# for_description.net
KiCad netlist of a schematic drawn in Altium Designer
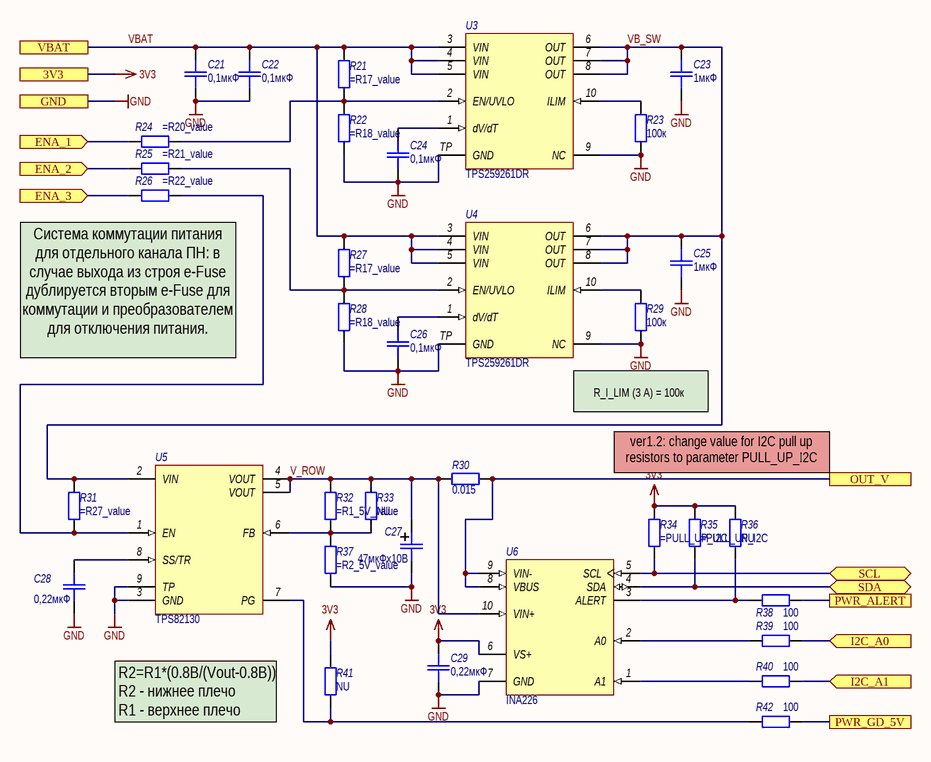
[diagram p0: for description.SchDoc]

(export (version "E")
  (design (tool "Eeschema 10.0.6"))
  (components
    (comp (ref "C21")
      (value "0,1мкФ")
      (footprint "CR-0603")
      (description "Конденсатор для поверхностного монтажа")
      (libsource (lib "my_passive") (part "C_smd"))
    )
    (comp (ref "C22")
      (value "0,1мкФ")
      (footprint "CR-0603")
      (description "Конденсатор для поверхностного монтажа")
      (libsource (lib "my_passive") (part "C_smd"))
    )
    (comp (ref "C23")
      (value "1мкФ")
      (footprint "CR-0603")
      (description "Конденсатор для поверхностного монтажа")
      (libsource (lib "my_passive") (part "C_smd"))
    )
    (comp (ref "C24")
      (value "0,1мкФ")
      (footprint "CR-0603")
      (description "Конденсатор для поверхностного монтажа")
      (libsource (lib "my_passive") (part "C_smd"))
    )
    (comp (ref "C25")
      (value "1мкФ")
      (footprint "CR-0603")
      (description "Конденсатор для поверхностного монтажа")
      (libsource (lib "my_passive") (part "C_smd"))
    )
    (comp (ref "C26")
      (value "0,1мкФ")
      (footprint "CR-0603")
      (description "Конденсатор для поверхностного монтажа")
      (libsource (lib "my_passive") (part "C_smd"))
    )
    (comp (ref "C27")
      (value "47мкФх10В")
      (footprint "C_SMD_SIZE_B")
      (description "Поляризованный конеднсатор для поверхностного монтажа")
      (libsource (lib "my_passive") (part "C_pol_smd"))
    )
    (comp (ref "C28")
      (value "0,22мкФ")
      (footprint "CR-0603")
      (description "Конденсатор для поверхностного монтажа")
      (libsource (lib "my_passive") (part "C_smd"))
    )
    (comp (ref "C29")
      (value "0,22мкФ")
      (footprint "CR-0603")
      (description "Конденсатор для поверхностного монтажа")
      (libsource (lib "my_passive") (part "C_smd"))
    )
    (comp (ref "R21")
      (value "R17_value")
      (footprint "CR-0603")
      (description "Резистор для поверхностного монтажа")
      (libsource (lib "my_passive") (part "R_smd"))
    )
    (comp (ref "R22")
      (value "R18_value")
      (footprint "CR-0603")
      (description "Резистор для поверхностного монтажа")
      (libsource (lib "my_passive") (part "R_smd"))
    )
    (comp (ref "R23")
      (value "100к")
      (footprint "CR-0603")
      (description "Резистор для поверхностного монтажа")
      (libsource (lib "") (part "R_smd_2"))
    )
    (comp (ref "R24")
      (value "~")
      (footprint "CR-0603")
      (description "Резистор для поверхностного монтажа")
      (libsource (lib "") (part "R_smd_1"))
    )
    (comp (ref "R25")
      (value "~")
      (footprint "CR-0603")
      (description "Резистор для поверхностного монтажа")
      (libsource (lib "") (part "R_smd_1"))
    )
    (comp (ref "R26")
      (value "~")
      (footprint "CR-0603")
      (description "Резистор для поверхностного монтажа")
      (libsource (lib "") (part "R_smd_1"))
    )
    (comp (ref "R27")
      (value "R17_value")
      (footprint "CR-0603")
      (description "Резистор для поверхностного монтажа")
      (libsource (lib "my_passive") (part "R_smd"))
    )
    (comp (ref "R28")
      (value "R18_value")
      (footprint "CR-0603")
      (description "Резистор для поверхностного монтажа")
      (libsource (lib "my_passive") (part "R_smd"))
    )
    (comp (ref "R29")
      (value "100к")
      (footprint "CR-0603")
      (description "Резистор для поверхностного монтажа")
      (libsource (lib "") (part "R_smd_2"))
    )
    (comp (ref "R30")
      (value "0.015")
      (footprint "CR-1206")
      (description "Резистор для поверхностного монтажа")
      (fields (field (name "Comment") "0,01"))
      (libsource (lib "") (part "R_smd_1"))
    )
    (comp (ref "R31")
      (value "~")
      (footprint "CR-0603")
      (description "Резистор для поверхностного монтажа")
      (libsource (lib "") (part "R_smd_2"))
    )
    (comp (ref "R32")
      (value "~")
      (footprint "CR-0603")
      (description "Резистор для поверхностного монтажа")
      (libsource (lib "") (part "R_smd_2"))
    )
    (comp (ref "R33")
      (value "NU")
      (footprint "CR-0603")
      (description "Резистор для поверхностного монтажа")
      (libsource (lib "") (part "R_smd_2"))
    )
    (comp (ref "R34")
      (value "~")
      (footprint "CR-0603")
      (description "Резистор для поверхностного монтажа")
      (libsource (lib "") (part "R_smd_2"))
    )
    (comp (ref "R35")
      (value "~")
      (footprint "CR-0603")
      (description "Резистор для поверхностного монтажа")
      (libsource (lib "") (part "R_smd_2"))
    )
    (comp (ref "R36")
      (value "NU")
      (footprint "CR-0603")
      (description "Резистор для поверхностного монтажа")
      (libsource (lib "") (part "R_smd_2"))
    )
    (comp (ref "R37")
      (value "~")
      (footprint "CR-0603")
      (description "Резистор для поверхностного монтажа")
      (libsource (lib "") (part "R_smd_2"))
    )
    (comp (ref "R38")
      (value "100")
      (footprint "CR-0603")
      (description "Резистор для поверхностного монтажа")
      (libsource (lib "") (part "R_smd_1"))
    )
    (comp (ref "R39")
      (value "100")
      (footprint "CR-0603")
      (description "Резистор для поверхностного монтажа")
      (libsource (lib "") (part "R_smd_1"))
    )
    (comp (ref "R40")
      (value "100")
      (footprint "CR-0603")
      (description "Резистор для поверхностного монтажа")
      (libsource (lib "") (part "R_smd_1"))
    )
    (comp (ref "R41")
      (value "NU")
      (footprint "CR-0603")
      (description "Резистор для поверхностного монтажа")
      (libsource (lib "") (part "R_smd_2"))
    )
    (comp (ref "R42")
      (value "100")
      (footprint "CR-0603")
      (description "Резистор для поверхностного монтажа")
      (libsource (lib "") (part "R_smd_1"))
    )
    (comp (ref "U3")
      (value "TPS259261ВК")
      (footprint "VSON-10")
      (description "Simple 5-V/12-V eFuse Protection Switches")
      (fields (field (name "НАИМЕНОВАНИЕ") "TPS259261DR"))
      (libsource (lib "my_power") (part "TPS259261"))
    )
    (comp (ref "U4")
      (value "TPS259261ВК")
      (footprint "VSON-10")
      (description "Simple 5-V/12-V eFuse Protection Switches")
      (fields (field (name "НАИМЕНОВАНИЕ") "TPS259261DR"))
      (libsource (lib "my_power") (part "TPS259261"))
    )
    (comp (ref "U5")
      (value "TPS82130")
      (footprint "uSiL-8")
      (description "17-V Input 3-A Step-Down Converter MicroSiP™ Module with Integrated Inductor")
      (fields (field (name "НАИМЕНОВАНИЕ") "TPS82130"))
      (libsource (lib "my_power") (part "TPS82130"))
    )
    (comp (ref "U6")
      (value "INA226")
      (footprint "VSSOP-8")
      (description "High- or Low-Side Measurement, Bidirectional Current and Power Monitor With I2C Interface")
      (fields (field (name "НАИМЕНОВАНИЕ") "INA226"))
      (libsource (lib "my_power") (part "INA226"))
    )
  )
  (nets
    (net (code "1") (name "/ENA_1") (class "Default")
      (node (ref "R24") (pin "2") (pinfunction "2_2") (pintype "passive"))
    )
    (net (code "2") (name "/ENA_2") (class "Default")
      (node (ref "R25") (pin "2") (pinfunction "2_2") (pintype "passive"))
    )
    (net (code "3") (name "/ENA_3") (class "Default")
      (node (ref "R26") (pin "2") (pinfunction "2_2") (pintype "passive"))
    )
    (net (code "4") (name "/I2C_A0") (class "Default")
      (node (ref "R39") (pin "1") (pinfunction "1_1") (pintype "passive"))
    )
    (net (code "5") (name "/I2C_A1") (class "Default")
      (node (ref "R40") (pin "1") (pinfunction "1_1") (pintype "passive"))
    )
    (net (code "6") (name "/OUT_V") (class "Default")
      (node (ref "R30") (pin "1") (pinfunction "1_1") (pintype "passive"))
      (node (ref "U6") (pin "8") (pinfunction "VBUS_8") (pintype "input"))
      (node (ref "U6") (pin "9") (pinfunction "VIN-_9") (pintype "input"))
    )
    (net (code "7") (name "/PWR_ALERT") (class "Default")
      (node (ref "R38") (pin "1") (pinfunction "1_1") (pintype "passive"))
    )
    (net (code "8") (name "/PWR_GD_5V") (class "Default")
      (node (ref "R42") (pin "1") (pinfunction "1_1") (pintype "passive"))
    )
    (net (code "9") (name "/SCL") (class "Default")
      (node (ref "R34") (pin "1") (pinfunction "1_1") (pintype "passive"))
      (node (ref "U6") (pin "5") (pinfunction "SCL_5") (pintype "input"))
    )
    (net (code "10") (name "/SDA") (class "Default")
      (node (ref "R35") (pin "1") (pinfunction "1_1") (pintype "passive"))
      (node (ref "U6") (pin "4") (pinfunction "SDA_4") (pintype "bidirectional"))
    )
    (net (code "11") (name "/VBAT") (class "Default")
      (node (ref "C21") (pin "2") (pinfunction "2_2") (pintype "passive"))
      (node (ref "C22") (pin "2") (pinfunction "2_2") (pintype "passive"))
      (node (ref "R21") (pin "1") (pinfunction "1_1") (pintype "passive"))
      (node (ref "R27") (pin "1") (pinfunction "1_1") (pintype "passive"))
      (node (ref "U3") (pin "3") (pinfunction "VIN_3") (pintype "power_in"))
      (node (ref "U3") (pin "4") (pinfunction "VIN_4") (pintype "power_in"))
      (node (ref "U3") (pin "5") (pinfunction "VIN_5") (pintype "power_in"))
      (node (ref "U4") (pin "3") (pinfunction "VIN_3") (pintype "power_in"))
      (node (ref "U4") (pin "4") (pinfunction "VIN_4") (pintype "power_in"))
      (node (ref "U4") (pin "5") (pinfunction "VIN_5") (pintype "power_in"))
    )
    (net (code "12") (name "/VB_SW") (class "Default")
      (node (ref "C23") (pin "2") (pinfunction "2_2") (pintype "passive"))
      (node (ref "C25") (pin "2") (pinfunction "2_2") (pintype "passive"))
      (node (ref "R31") (pin "2") (pinfunction "2_2") (pintype "passive"))
      (node (ref "U3") (pin "6") (pinfunction "OUT_6") (pintype "power_in"))
      (node (ref "U3") (pin "7") (pinfunction "OUT_7") (pintype "power_in"))
      (node (ref "U3") (pin "8") (pinfunction "OUT_8") (pintype "power_in"))
      (node (ref "U4") (pin "6") (pinfunction "OUT_6") (pintype "power_in"))
      (node (ref "U4") (pin "7") (pinfunction "OUT_7") (pintype "power_in"))
      (node (ref "U4") (pin "8") (pinfunction "OUT_8") (pintype "power_in"))
      (node (ref "U5") (pin "2") (pinfunction "VIN_2") (pintype "power_in"))
    )
    (net (code "13") (name "/V_ROW") (class "Default")
      (node (ref "C27") (pin "1") (pinfunction "1_1") (pintype "passive"))
      (node (ref "R30") (pin "2") (pinfunction "2_2") (pintype "passive"))
      (node (ref "R32") (pin "2") (pinfunction "2_2") (pintype "passive"))
      (node (ref "R33") (pin "2") (pinfunction "2_2") (pintype "passive"))
      (node (ref "U5") (pin "4") (pinfunction "VOUT_4") (pintype "power_in"))
      (node (ref "U5") (pin "5") (pinfunction "VOUT_5") (pintype "power_in"))
      (node (ref "U6") (pin "10") (pinfunction "VIN+_10") (pintype "input"))
    )
    (net (code "14") (name "3V3") (class "Default")
      (node (ref "C29") (pin "2") (pinfunction "2_2") (pintype "passive"))
      (node (ref "R34") (pin "2") (pinfunction "2_2") (pintype "passive"))
      (node (ref "R35") (pin "2") (pinfunction "2_2") (pintype "passive"))
      (node (ref "R36") (pin "2") (pinfunction "2_2") (pintype "passive"))
      (node (ref "R41") (pin "2") (pinfunction "2_2") (pintype "passive"))
      (node (ref "U6") (pin "6") (pinfunction "VS+_6") (pintype "power_in"))
    )
    (net (code "15") (name "GND") (class "Default")
      (node (ref "C21") (pin "1") (pinfunction "1_1") (pintype "passive"))
      (node (ref "C22") (pin "1") (pinfunction "1_1") (pintype "passive"))
      (node (ref "C23") (pin "1") (pinfunction "1_1") (pintype "passive"))
      (node (ref "C24") (pin "1") (pinfunction "1_1") (pintype "passive"))
      (node (ref "C25") (pin "1") (pinfunction "1_1") (pintype "passive"))
      (node (ref "C26") (pin "1") (pinfunction "1_1") (pintype "passive"))
      (node (ref "C27") (pin "2") (pinfunction "2_2") (pintype "passive"))
      (node (ref "C28") (pin "1") (pinfunction "1_1") (pintype "passive"))
      (node (ref "C29") (pin "1") (pinfunction "1_1") (pintype "passive"))
      (node (ref "R22") (pin "2") (pinfunction "2_2") (pintype "passive"))
      (node (ref "R23") (pin "1") (pinfunction "1_1") (pintype "passive"))
      (node (ref "R28") (pin "2") (pinfunction "2_2") (pintype "passive"))
      (node (ref "R29") (pin "1") (pinfunction "1_1") (pintype "passive"))
      (node (ref "R37") (pin "1") (pinfunction "1_1") (pintype "passive"))
      (node (ref "U3") (pin "9") (pinfunction "NC_9") (pintype "passive"))
      (node (ref "U3") (pin "TP") (pinfunction "GND_TP") (pintype "power_in"))
      (node (ref "U4") (pin "9") (pinfunction "NC_9") (pintype "passive"))
      (node (ref "U4") (pin "TP") (pinfunction "GND_TP") (pintype "power_in"))
      (node (ref "U5") (pin "3") (pinfunction "GND_3") (pintype "power_in"))
      (node (ref "U5") (pin "9") (pinfunction "TP_9") (pintype "power_in"))
      (node (ref "U6") (pin "7") (pinfunction "GND_7") (pintype "power_in"))
    )
    (net (code "16") (name "Net-(U3-EN{slash}UVLO)") (class "Default")
      (node (ref "R21") (pin "2") (pinfunction "2_2") (pintype "passive"))
      (node (ref "R22") (pin "1") (pinfunction "1_1") (pintype "passive"))
      (node (ref "R24") (pin "1") (pinfunction "1_1") (pintype "passive"))
      (node (ref "U3") (pin "2") (pinfunction "EN/UVLO_2") (pintype "input"))
    )
    (net (code "17") (name "Net-(U3-ILIM)") (class "Default")
      (node (ref "R23") (pin "2") (pinfunction "2_2") (pintype "passive"))
      (node (ref "U3") (pin "10") (pinfunction "ILIM_10") (pintype "input"))
    )
    (net (code "18") (name "Net-(U3-dV{slash}dT)") (class "Default")
      (node (ref "C24") (pin "2") (pinfunction "2_2") (pintype "passive"))
      (node (ref "U3") (pin "1") (pinfunction "dV/dT_1") (pintype "input"))
    )
    (net (code "19") (name "Net-(U4-EN{slash}UVLO)") (class "Default")
      (node (ref "R25") (pin "1") (pinfunction "1_1") (pintype "passive"))
      (node (ref "R27") (pin "2") (pinfunction "2_2") (pintype "passive"))
      (node (ref "R28") (pin "1") (pinfunction "1_1") (pintype "passive"))
      (node (ref "U4") (pin "2") (pinfunction "EN/UVLO_2") (pintype "input"))
    )
    (net (code "20") (name "Net-(U4-ILIM)") (class "Default")
      (node (ref "R29") (pin "2") (pinfunction "2_2") (pintype "passive"))
      (node (ref "U4") (pin "10") (pinfunction "ILIM_10") (pintype "input"))
    )
    (net (code "21") (name "Net-(U4-dV{slash}dT)") (class "Default")
      (node (ref "C26") (pin "2") (pinfunction "2_2") (pintype "passive"))
      (node (ref "U4") (pin "1") (pinfunction "dV/dT_1") (pintype "input"))
    )
    (net (code "22") (name "Net-(U5-EN)") (class "Default")
      (node (ref "R26") (pin "1") (pinfunction "1_1") (pintype "passive"))
      (node (ref "R31") (pin "1") (pinfunction "1_1") (pintype "passive"))
      (node (ref "U5") (pin "1") (pinfunction "EN_1") (pintype "input"))
    )
    (net (code "23") (name "Net-(U5-FB)") (class "Default")
      (node (ref "R32") (pin "1") (pinfunction "1_1") (pintype "passive"))
      (node (ref "R33") (pin "1") (pinfunction "1_1") (pintype "passive"))
      (node (ref "R37") (pin "2") (pinfunction "2_2") (pintype "passive"))
      (node (ref "U5") (pin "6") (pinfunction "FB_6") (pintype "input"))
    )
    (net (code "24") (name "Net-(U5-PG)") (class "Default")
      (node (ref "R41") (pin "1") (pinfunction "1_1") (pintype "passive"))
      (node (ref "R42") (pin "2") (pinfunction "2_2") (pintype "passive"))
      (node (ref "U5") (pin "7") (pinfunction "PG_7") (pintype "open_collector"))
    )
    (net (code "25") (name "Net-(U5-SS{slash}TR)") (class "Default")
      (node (ref "C28") (pin "2") (pinfunction "2_2") (pintype "passive"))
      (node (ref "U5") (pin "8") (pinfunction "SS/TR_8") (pintype "input"))
    )
    (net (code "26") (name "Net-(U6-A0)") (class "Default")
      (node (ref "R39") (pin "2") (pinfunction "2_2") (pintype "passive"))
      (node (ref "U6") (pin "2") (pinfunction "A0_2") (pintype "input"))
    )
    (net (code "27") (name "Net-(U6-A1)") (class "Default")
      (node (ref "R40") (pin "2") (pinfunction "2_2") (pintype "passive"))
      (node (ref "U6") (pin "1") (pinfunction "A1_1") (pintype "input"))
    )
    (net (code "28") (name "Net-(U6-ALERT)") (class "Default")
      (node (ref "R36") (pin "1") (pinfunction "1_1") (pintype "passive"))
      (node (ref "R38") (pin "2") (pinfunction "2_2") (pintype "passive"))
      (node (ref "U6") (pin "3") (pinfunction "ALERT_3") (pintype "open_collector"))
    )
  )
)
